# JTAG.net
KiCad netlist of a schematic drawn in Altium Designer
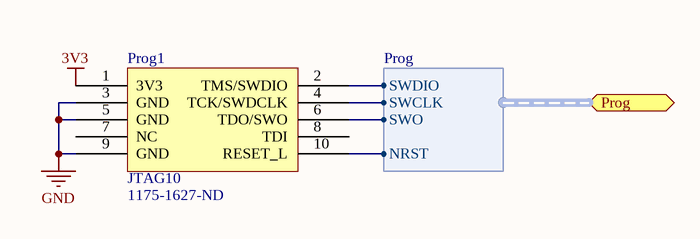
[diagram p0: JTAG.SchDoc]

(export (version "E")
  (design (tool "Eeschema 10.0.6"))
  (components
    (comp (ref "Prog1")
      (value "JTAG10")
      (footprint "JTAG10 Polarity")
      (description "3220-10-0100-00")
      (fields (field (name "SUPPLIER PART NUMBER 1") "1175-1627-ND"))
      (libsource (lib "CornellBajaLibrary") (part "JTAG10"))
    )
  )
  (nets
    (net (code "2") (name "/NRST") (class "Default")
      (node (ref "Prog1") (pin "10") (pinfunction "RESET_L_10") (pintype "passive"))
    )
    (net (code "3") (name "/SWCLK") (class "Default")
      (node (ref "Prog1") (pin "4") (pinfunction "TCK/SWDCLK_4") (pintype "passive"))
    )
    (net (code "4") (name "/SWDIO") (class "Default")
      (node (ref "Prog1") (pin "2") (pinfunction "TMS/SWDIO_2") (pintype "passive"))
    )
    (net (code "5") (name "/SWO") (class "Default")
      (node (ref "Prog1") (pin "6") (pinfunction "TDO/SWO_6") (pintype "passive"))
    )
    (net (code "7") (name "3V3") (class "Default")
      (node (ref "Prog1") (pin "1") (pinfunction "3V3_1") (pintype "passive"))
    )
    (net (code "8") (name "GND") (class "Default")
      (node (ref "Prog1") (pin "3") (pinfunction "GND_3") (pintype "passive"))
      (node (ref "Prog1") (pin "5") (pinfunction "GND_5") (pintype "passive"))
      (node (ref "Prog1") (pin "9") (pinfunction "GND_9") (pintype "passive"))
    )
    (net (code "9") (name "unconnected-(Prog1-NC-Pad7)") (class "Default")
      (node (ref "Prog1") (pin "7") (pinfunction "NC_7") (pintype "passive"))
    )
    (net (code "10") (name "unconnected-(Prog1-TDI-Pad8)") (class "Default")
      (node (ref "Prog1") (pin "8") (pinfunction "TDI_8") (pintype "passive"))
    )
  )
)
